# Sheet1.net
KiCad netlist of a schematic drawn in Altium Designer
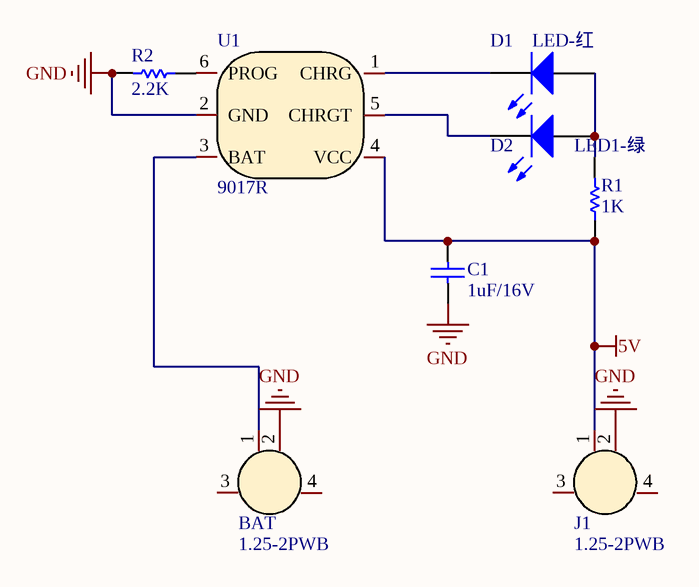
[diagram p0: Sheet1.SchDoc]

(export (version "E")
  (design (tool "Eeschema 10.0.6"))
  (components
    (comp (ref "BAT")
      (value "1.25-2PWB")
      (footprint "MX 1.25-LS-2P")
      (libsource (lib "Schlib1") (part "1.25-2PWB"))
    )
    (comp (ref "C1")
      (value "1uF/16V")
      (footprint "6-0805_M")
      (description "Capacitor")
      (fields (field (name "PUBLISHER") "Altium Limited"))
      (libsource (lib "Miscellaneous Devices") (part "Cap"))
    )
    (comp (ref "D1")
      (value "LED-红")
      (footprint "LED0805-RD_GREEN")
      (description "Typical RED GaAs LED")
      (fields (field (name "PUBLISHER") "Altium Limited"))
      (libsource (lib "Miscellaneous Devices") (part "LED1"))
    )
    (comp (ref "D2")
      (value "LED1-绿")
      (footprint "LED0805-RD_GREEN")
      (description "Typical RED GaAs LED")
      (fields (field (name "PUBLISHER") "Altium Limited"))
      (libsource (lib "Miscellaneous Devices") (part "LED1"))
    )
    (comp (ref "J1")
      (value "1.25-2PWB")
      (footprint "MX 1.25-LS-2P")
      (libsource (lib "Schlib1") (part "1.25-2PWB"))
    )
    (comp (ref "R1")
      (value "1K")
      (footprint "6-0805_M")
      (description "Resistor")
      (fields (field (name "PUBLISHER") "Altium Limited"))
      (libsource (lib "Miscellaneous Devices") (part "Res1"))
    )
    (comp (ref "R2")
      (value "2.2K")
      (footprint "6-0805_M")
      (description "Resistor")
      (fields (field (name "PUBLISHER") "Altium Limited"))
      (libsource (lib "Miscellaneous Devices") (part "Res1"))
    )
    (comp (ref "U1") (value "9017R") (libsource (lib "Schlib1") (part "9017R")))
  )
  (nets
    (net (code "1") (name "5V") (class "Default")
      (node (ref "C1") (pin "2") (pinfunction "2_2") (pintype "passive"))
      (node (ref "J1") (pin "1") (pinfunction "1_1") (pintype "passive"))
      (node (ref "R1") (pin "1") (pinfunction "1_1") (pintype "passive"))
      (node (ref "U1") (pin "4") (pinfunction "VCC_4") (pintype "passive"))
    )
    (net (code "2") (name "GND") (class "Default")
      (node (ref "BAT") (pin "2") (pinfunction "2_2") (pintype "passive"))
      (node (ref "C1") (pin "1") (pinfunction "1_1") (pintype "passive"))
      (node (ref "J1") (pin "2") (pinfunction "2_2") (pintype "passive"))
      (node (ref "R2") (pin "2") (pinfunction "2_2") (pintype "passive"))
      (node (ref "U1") (pin "2") (pinfunction "GND_2") (pintype "passive"))
    )
    (net (code "3") (name "Net-(D1-A)") (class "Default")
      (node (ref "D1") (pin "1") (pinfunction "A_1") (pintype "passive"))
      (node (ref "D2") (pin "1") (pinfunction "A_1") (pintype "passive"))
      (node (ref "R1") (pin "2") (pinfunction "2_2") (pintype "passive"))
    )
    (net (code "4") (name "Net-(D1-K)") (class "Default")
      (node (ref "D1") (pin "2") (pinfunction "K_2") (pintype "passive"))
      (node (ref "U1") (pin "1") (pinfunction "CHRG_1") (pintype "passive"))
    )
    (net (code "5") (name "Net-(D2-K)") (class "Default")
      (node (ref "D2") (pin "2") (pinfunction "K_2") (pintype "passive"))
      (node (ref "U1") (pin "5") (pinfunction "CHRGT_5") (pintype "passive"))
    )
    (net (code "6") (name "Net-(U1-BAT)") (class "Default")
      (node (ref "BAT") (pin "1") (pinfunction "1_1") (pintype "passive"))
      (node (ref "U1") (pin "3") (pinfunction "BAT_3") (pintype "passive"))
    )
    (net (code "7") (name "Net-(U1-PROG)") (class "Default")
      (node (ref "R2") (pin "1") (pinfunction "1_1") (pintype "passive"))
      (node (ref "U1") (pin "6") (pinfunction "PROG_6") (pintype "passive"))
    )
    (net (code "8") (name "unconnected-(BAT-Pad3)") (class "Default")
      (node (ref "BAT") (pin "3") (pinfunction "3_3") (pintype "passive"))
    )
    (net (code "9") (name "unconnected-(BAT-Pad4)") (class "Default")
      (node (ref "BAT") (pin "4") (pinfunction "4_4") (pintype "passive"))
    )
    (net (code "10") (name "unconnected-(J1-Pad3)") (class "Default")
      (node (ref "J1") (pin "3") (pinfunction "3_3") (pintype "passive"))
    )
    (net (code "11") (name "unconnected-(J1-Pad4)") (class "Default")
      (node (ref "J1") (pin "4") (pinfunction "4_4") (pintype "passive"))
    )
  )
)
